# LMP848x_Breakout_v1_2.net
KiCad netlist of a schematic drawn in EAGLE
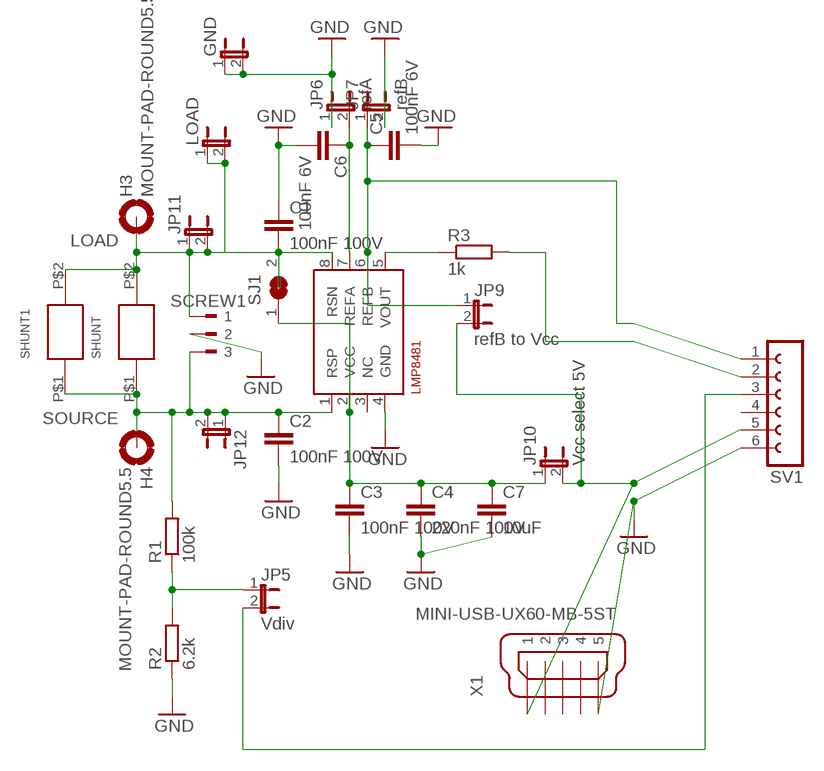
[diagram p0: schematic, sheet 1]

(export (version "E")
  (design (tool "Eeschema 10.0.6"))
  (components
    (comp (ref "C1")
      (value "100nF 100V")
      (footprint "eagle-import:C0805")
      (libsource (lib "eagle-import") (part "C-EUC0805"))
    )
    (comp (ref "C2")
      (value "100nF 100V")
      (footprint "eagle-import:C0805")
      (libsource (lib "eagle-import") (part "C-EUC0805"))
    )
    (comp (ref "C3")
      (value "100nF 100V")
      (footprint "eagle-import:C0805")
      (libsource (lib "eagle-import") (part "C-EUC0805"))
    )
    (comp (ref "C4")
      (value "220nF 100V")
      (footprint "eagle-import:C0805")
      (libsource (lib "eagle-import") (part "C-EUC0805"))
    )
    (comp (ref "C5")
      (value "100nF 6V")
      (footprint "eagle-import:C0805")
      (libsource (lib "eagle-import") (part "C-EUC0805"))
    )
    (comp (ref "C6")
      (value "100nF 6V")
      (footprint "eagle-import:C0805")
      (libsource (lib "eagle-import") (part "C-EUC0805"))
    )
    (comp (ref "C7")
      (value "10uF")
      (footprint "eagle-import:C025-024X044")
      (libsource (lib "eagle-import") (part "C-EU025-024X044"))
    )
    (comp (ref "GND")
      (value "JP1E")
      (footprint "eagle-import:JP1")
      (libsource (lib "eagle-import") (part "JP1E"))
    )
    (comp (ref "H3")
      (value "MOUNT-PAD-ROUND5.5")
      (footprint "eagle-import:5,5-PAD")
      (libsource (lib "eagle-import") (part "MOUNT-PAD-ROUND5.5"))
    )
    (comp (ref "H4")
      (value "MOUNT-PAD-ROUND5.5")
      (footprint "eagle-import:5,5-PAD")
      (libsource (lib "eagle-import") (part "MOUNT-PAD-ROUND5.5"))
    )
    (comp (ref "JP5")
      (value "Vdiv")
      (footprint "eagle-import:JP1")
      (libsource (lib "eagle-import") (part "JP1E"))
    )
    (comp (ref "JP6")
      (value "refA")
      (footprint "eagle-import:JP1")
      (libsource (lib "eagle-import") (part "JP1E"))
    )
    (comp (ref "JP7")
      (value "refB")
      (footprint "eagle-import:JP1")
      (libsource (lib "eagle-import") (part "JP1E"))
    )
    (comp (ref "JP9")
      (value "refB to Vcc")
      (footprint "eagle-import:JP1")
      (libsource (lib "eagle-import") (part "JP1E"))
    )
    (comp (ref "JP10")
      (value "Vcc select 5V")
      (footprint "eagle-import:JP1")
      (libsource (lib "eagle-import") (part "JP1E"))
    )
    (comp (ref "JP11")
      (value "JP1E")
      (footprint "eagle-import:JP1")
      (libsource (lib "eagle-import") (part "JP1E"))
    )
    (comp (ref "JP12")
      (value "JP1E")
      (footprint "eagle-import:JP1")
      (libsource (lib "eagle-import") (part "JP1E"))
    )
    (comp (ref "LMP8481")
      (value "LMP8481-H")
      (footprint "eagle-import:S-PDSO-G08")
      (libsource (lib "eagle-import") (part "LMP8481-H"))
    )
    (comp (ref "LOAD")
      (value "JP1E")
      (footprint "eagle-import:JP1")
      (libsource (lib "eagle-import") (part "JP1E"))
    )
    (comp (ref "R1")
      (value "100k")
      (footprint "eagle-import:0207_10")
      (libsource (lib "eagle-import") (part "R-EU_0207/10"))
    )
    (comp (ref "R2")
      (value "6.2k")
      (footprint "eagle-import:0204_5")
      (libsource (lib "eagle-import") (part "R-EU_0204/5"))
    )
    (comp (ref "R3")
      (value "1k")
      (footprint "eagle-import:0204_5")
      (libsource (lib "eagle-import") (part "R-EU_0204/5"))
    )
    (comp (ref "SCREW1")
      (value "180-3")
      (footprint "eagle-import:180-3")
      (libsource (lib "eagle-import") (part "180-3"))
    )
    (comp (ref "SHUNT")
      (value "EBW_SERIES_15.2MM")
      (footprint "eagle-import:EBW_SERIES_15.2MM")
      (libsource (lib "eagle-import") (part "EBW_SERIES_15.2MM"))
    )
    (comp (ref "SHUNT1")
      (value "EBW_SERIES_15.2MM")
      (footprint "eagle-import:EBW_SERIES_15.2MM")
      (libsource (lib "eagle-import") (part "EBW_SERIES_15.2MM"))
    )
    (comp (ref "SJ1") (value "SJ") (footprint "eagle-import:SJ") (libsource (lib "eagle-import") (part "SJ")))
    (comp (ref "SV1")
      (value "FE06-1")
      (footprint "eagle-import:FE06")
      (libsource (lib "eagle-import") (part "FE06-1"))
    )
    (comp (ref "X1")
      (value "MINI-USB-UX60-MB-5ST")
      (footprint "eagle-import:UX60-MB-5ST")
      (libsource (lib "eagle-import") (part "MINI-USB-UX60-MB-5ST"))
    )
  )
  (nets
    (net (code "1") (name "/LOAD") (class "Default")
      (node (ref "C1") (pin "2") (pinfunction "2_2") (pintype "passive"))
      (node (ref "H3") (pin "B5,5") (pinfunction "MOUNT_B5,5") (pintype "passive"))
      (node (ref "JP11") (pin "1") (pinfunction "1_1") (pintype "passive"))
      (node (ref "JP11") (pin "2") (pinfunction "2_2") (pintype "passive"))
      (node (ref "LMP8481") (pin "8") (pinfunction "RSN_8") (pintype "bidirectional"))
      (node (ref "LOAD") (pin "1") (pinfunction "1_1") (pintype "passive"))
      (node (ref "LOAD") (pin "2") (pinfunction "2_2") (pintype "passive"))
      (node (ref "SCREW1") (pin "1") (pinfunction "1_1") (pintype "passive"))
      (node (ref "SHUNT") (pin "P$2") (pinfunction "P$2_P$2") (pintype "bidirectional"))
      (node (ref "SHUNT1") (pin "P$2") (pinfunction "P$2_P$2") (pintype "bidirectional"))
      (node (ref "SJ1") (pin "2") (pinfunction "2_2") (pintype "passive"))
    )
    (net (code "2") (name "/SOURCE") (class "Default")
      (node (ref "C2") (pin "1") (pinfunction "1_1") (pintype "passive"))
      (node (ref "H4") (pin "B5,5") (pinfunction "MOUNT_B5,5") (pintype "passive"))
      (node (ref "JP12") (pin "1") (pinfunction "1_1") (pintype "passive"))
      (node (ref "JP12") (pin "2") (pinfunction "2_2") (pintype "passive"))
      (node (ref "LMP8481") (pin "1") (pinfunction "RSP_1") (pintype "bidirectional"))
      (node (ref "R1") (pin "2") (pinfunction "2_2") (pintype "passive"))
      (node (ref "SCREW1") (pin "3") (pinfunction "3_3") (pintype "passive"))
      (node (ref "SHUNT") (pin "P$1") (pinfunction "P$1_P$1") (pintype "bidirectional"))
      (node (ref "SHUNT1") (pin "P$1") (pinfunction "P$1_P$1") (pintype "bidirectional"))
    )
    (net (code "3") (name "GND") (class "Default")
      (node (ref "C1") (pin "1") (pinfunction "1_1") (pintype "passive"))
      (node (ref "C2") (pin "2") (pinfunction "2_2") (pintype "passive"))
      (node (ref "C3") (pin "2") (pinfunction "2_2") (pintype "passive"))
      (node (ref "C4") (pin "2") (pinfunction "2_2") (pintype "passive"))
      (node (ref "C5") (pin "2") (pinfunction "2_2") (pintype "passive"))
      (node (ref "C6") (pin "2") (pinfunction "2_2") (pintype "passive"))
      (node (ref "C7") (pin "2") (pinfunction "2_2") (pintype "passive"))
      (node (ref "GND") (pin "1") (pinfunction "1_1") (pintype "passive"))
      (node (ref "GND") (pin "2") (pinfunction "2_2") (pintype "passive"))
      (node (ref "JP6") (pin "1") (pinfunction "1_1") (pintype "passive"))
      (node (ref "JP7") (pin "2") (pinfunction "2_2") (pintype "passive"))
      (node (ref "LMP8481") (pin "4") (pinfunction "GND_4") (pintype "bidirectional"))
      (node (ref "R2") (pin "1") (pinfunction "1_1") (pintype "passive"))
      (node (ref "SCREW1") (pin "2") (pinfunction "2_2") (pintype "passive"))
      (node (ref "SV1") (pin "6") (pinfunction "6_6") (pintype "passive"))
      (node (ref "X1") (pin "5") (pinfunction "5_5") (pintype "input"))
    )
    (net (code "4") (name "Net-(JP5-Pad1)") (class "Default")
      (node (ref "JP5") (pin "1") (pinfunction "1_1") (pintype "passive"))
      (node (ref "R1") (pin "1") (pinfunction "1_1") (pintype "passive"))
      (node (ref "R2") (pin "2") (pinfunction "2_2") (pintype "passive"))
    )
    (net (code "5") (name "Net-(JP5-Pad2)") (class "Default")
      (node (ref "JP5") (pin "2") (pinfunction "2_2") (pintype "passive"))
      (node (ref "SV1") (pin "3") (pinfunction "3_3") (pintype "passive"))
    )
    (net (code "6") (name "Net-(JP10-Pad2)") (class "Default")
      (node (ref "JP10") (pin "2") (pinfunction "2_2") (pintype "passive"))
      (node (ref "JP9") (pin "2") (pinfunction "2_2") (pintype "passive"))
      (node (ref "SV1") (pin "5") (pinfunction "5_5") (pintype "passive"))
      (node (ref "X1") (pin "1") (pinfunction "1_1") (pintype "input"))
    )
    (net (code "7") (name "Net-(LMP8481-REFA)") (class "Default")
      (node (ref "C6") (pin "1") (pinfunction "1_1") (pintype "passive"))
      (node (ref "JP6") (pin "2") (pinfunction "2_2") (pintype "passive"))
      (node (ref "LMP8481") (pin "7") (pinfunction "REFA_7") (pintype "bidirectional"))
    )
    (net (code "8") (name "Net-(LMP8481-REFB)") (class "Default")
      (node (ref "C5") (pin "1") (pinfunction "1_1") (pintype "passive"))
      (node (ref "JP7") (pin "1") (pinfunction "1_1") (pintype "passive"))
      (node (ref "JP9") (pin "1") (pinfunction "1_1") (pintype "passive"))
      (node (ref "LMP8481") (pin "6") (pinfunction "REFB_6") (pintype "bidirectional"))
      (node (ref "SV1") (pin "1") (pinfunction "1_1") (pintype "passive"))
    )
    (net (code "9") (name "Net-(LMP8481-VCC)") (class "Default")
      (node (ref "C3") (pin "1") (pinfunction "1_1") (pintype "passive"))
      (node (ref "C4") (pin "1") (pinfunction "1_1") (pintype "passive"))
      (node (ref "C7") (pin "1") (pinfunction "1_1") (pintype "passive"))
      (node (ref "JP10") (pin "1") (pinfunction "1_1") (pintype "passive"))
      (node (ref "LMP8481") (pin "2") (pinfunction "VCC_2") (pintype "bidirectional"))
      (node (ref "SJ1") (pin "1") (pinfunction "1_1") (pintype "passive"))
    )
    (net (code "10") (name "Net-(LMP8481-VOUT)") (class "Default")
      (node (ref "LMP8481") (pin "5") (pinfunction "VOUT_5") (pintype "bidirectional"))
      (node (ref "R3") (pin "1") (pinfunction "1_1") (pintype "passive"))
    )
    (net (code "11") (name "Net-(R3-Pad2)") (class "Default")
      (node (ref "R3") (pin "2") (pinfunction "2_2") (pintype "passive"))
      (node (ref "SV1") (pin "2") (pinfunction "2_2") (pintype "passive"))
    )
    (net (code "12") (name "unconnected-(LMP8481-NC-Pad3)") (class "Default")
      (node (ref "LMP8481") (pin "3") (pinfunction "NC_3") (pintype "bidirectional"))
    )
    (net (code "13") (name "unconnected-(SV1-Pad4)") (class "Default")
      (node (ref "SV1") (pin "4") (pinfunction "4_4") (pintype "passive"))
    )
    (net (code "14") (name "unconnected-(X1-Pad2)") (class "Default")
      (node (ref "X1") (pin "2") (pinfunction "2_2") (pintype "input"))
    )
    (net (code "15") (name "unconnected-(X1-Pad3)") (class "Default")
      (node (ref "X1") (pin "3") (pinfunction "3_3") (pintype "input"))
    )
    (net (code "16") (name "unconnected-(X1-Pad4)") (class "Default")
      (node (ref "X1") (pin "4") (pinfunction "4_4") (pintype "input"))
    )
  )
)
